# mod-mag.net
KiCad netlist of a schematic drawn in Altium Designer
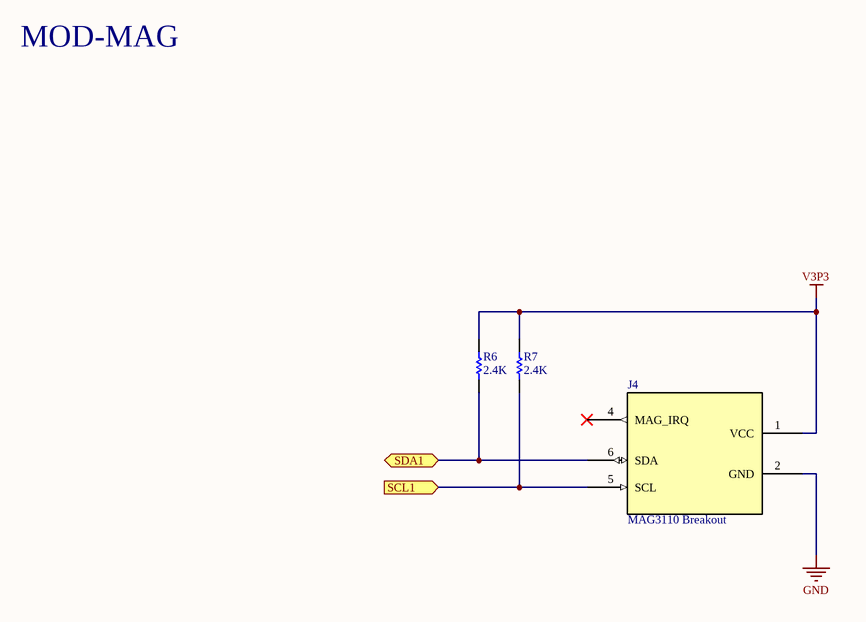
[diagram p0: mod-mag.SchDoc]

(export (version "E")
  (design (tool "Eeschema 10.0.6"))
  (components
    (comp (ref "J4")
      (value "MAG3110 Breakout")
      (footprint "UEXT_MALE x10")
      (libsource (lib "Schlib") (part "MOD-MAG3110"))
    )
    (comp (ref "R6")
      (value "2.4K")
      (footprint "own_0603")
      (description "Resistor")
      (libsource (lib "Miscellaneous Devices") (part "Res1"))
    )
    (comp (ref "R7")
      (value "2.4K")
      (footprint "own_0603")
      (description "Resistor")
      (libsource (lib "Miscellaneous Devices") (part "Res1"))
    )
  )
  (nets
    (net (code "1") (name "/SCL1") (class "Default")
      (node (ref "J4") (pin "5") (pinfunction "SCL_5") (pintype "input"))
      (node (ref "R7") (pin "1") (pinfunction "1_1") (pintype "passive"))
    )
    (net (code "2") (name "/SDA1") (class "Default")
      (node (ref "J4") (pin "6") (pinfunction "SDA_6") (pintype "bidirectional"))
      (node (ref "R6") (pin "1") (pinfunction "1_1") (pintype "passive"))
    )
    (net (code "3") (name "GND") (class "Default")
      (node (ref "J4") (pin "2") (pinfunction "GND_2") (pintype "power_in"))
    )
    (net (code "4") (name "V3P3") (class "Default")
      (node (ref "J4") (pin "1") (pinfunction "VCC_1") (pintype "power_in"))
      (node (ref "R6") (pin "2") (pinfunction "2_2") (pintype "passive"))
      (node (ref "R7") (pin "2") (pinfunction "2_2") (pintype "passive"))
    )
    (net (code "5") (name "unconnected-(J4-MAG_IRQ-Pad4)") (class "Default")
      (node (ref "J4") (pin "4") (pinfunction "MAG_IRQ_4") (pintype "output+no_connect"))
    )
  )
)
